# Rain_Collector_Inside_v2.net
KiCad netlist of a schematic drawn in EAGLE
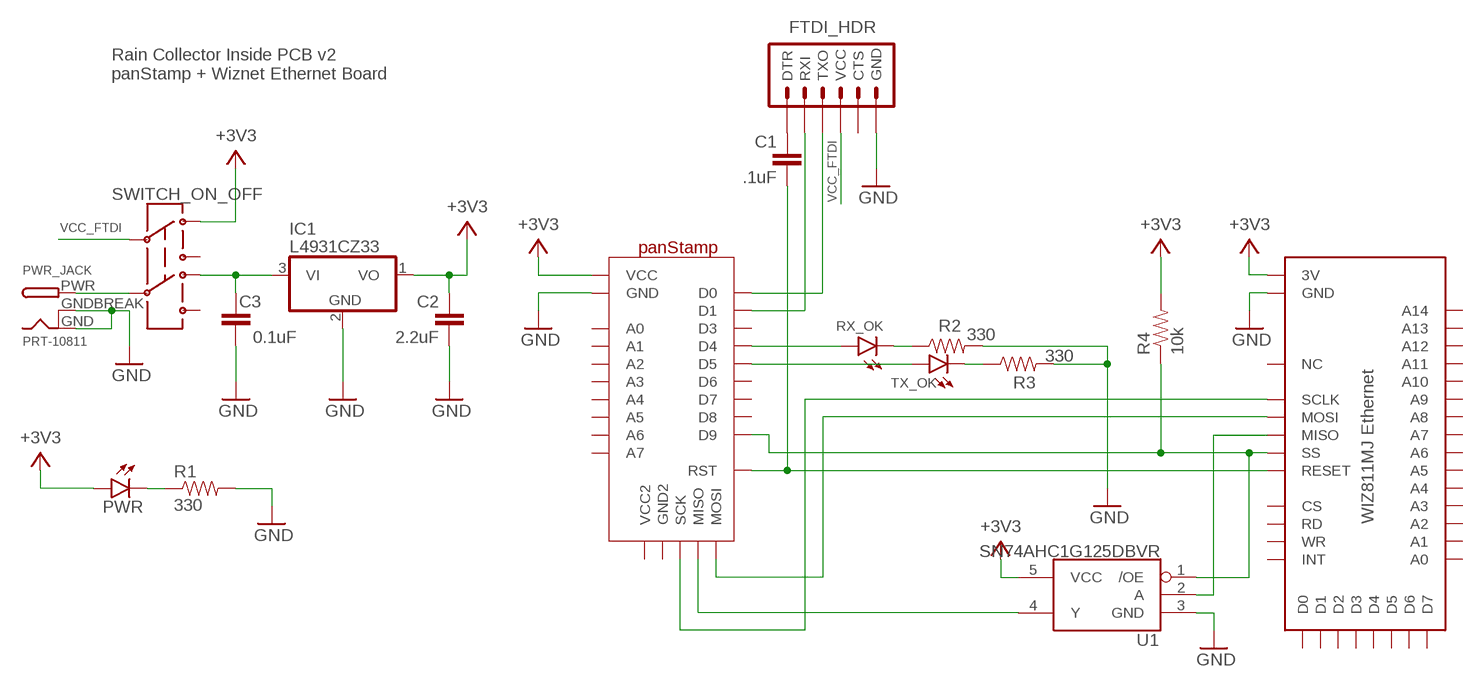
[diagram p0: schematic, sheet 1]

(export (version "E")
  (design (tool "Eeschema 10.0.6"))
  (components
    (comp (ref "C1")
      (value ".1uF")
      (footprint "eagle-import:CAP-PTH-5MM")
      (libsource (lib "eagle-import") (part "CAPPTH1"))
    )
    (comp (ref "C2")
      (value "2.2uF")
      (footprint "eagle-import:CAP-PTH-5MM")
      (libsource (lib "eagle-import") (part "CAPPTH1"))
    )
    (comp (ref "C3")
      (value "0.1uF")
      (footprint "eagle-import:CAP-PTH-5MM")
      (libsource (lib "eagle-import") (part "CAPPTH1"))
    )
    (comp (ref "FTDI_HDR")
      (value "ARDUINO_SERIAL_PROGRAMLONGPADS")
      (footprint "eagle-import:1X06_LONGPADS")
      (libsource (lib "eagle-import") (part "ARDUINO_SERIAL_PROGRAMLONGPADS"))
    )
    (comp (ref "IC1")
      (value "L4931CZ33")
      (footprint "eagle-import:TO92")
      (libsource (lib "eagle-import") (part "78ZL15"))
    )
    (comp (ref "PANSTAMP")
      (value "PANSTAMP_SPI")
      (footprint "eagle-import:PANSTAMP_SPI")
      (libsource (lib "eagle-import") (part "PANSTAMP_SPI"))
    )
    (comp (ref "PWR")
      (value "LED5MM")
      (footprint "eagle-import:LED5MM")
      (libsource (lib "eagle-import") (part "LED5MM"))
    )
    (comp (ref "PWR_JACK")
      (value "PRT-10811")
      (footprint "eagle-import:DCJACK_2MM_PTH")
      (libsource (lib "eagle-import") (part "DCBARRELPTH"))
    )
    (comp (ref "R1")
      (value "330")
      (footprint "eagle-import:AXIAL-0.4")
      (libsource (lib "eagle-import") (part "RESISTORPTH-1/4W"))
    )
    (comp (ref "R2")
      (value "330")
      (footprint "eagle-import:AXIAL-0.4")
      (libsource (lib "eagle-import") (part "RESISTORPTH-1/4W"))
    )
    (comp (ref "R3")
      (value "330")
      (footprint "eagle-import:AXIAL-0.4")
      (libsource (lib "eagle-import") (part "RESISTORPTH-1/4W"))
    )
    (comp (ref "R4")
      (value "10k")
      (footprint "eagle-import:AXIAL-0.4")
      (libsource (lib "eagle-import") (part "RESISTORPTH-1/4W"))
    )
    (comp (ref "RX_OK")
      (value "LED5MM")
      (footprint "eagle-import:LED5MM")
      (libsource (lib "eagle-import") (part "LED5MM"))
    )
    (comp (ref "SWITCH_ON_OFF")
      (value "401-2001-ND")
      (footprint "eagle-import:SWITCH_DPDT_PTH")
      (libsource (lib "eagle-import") (part "SWITCH_DPDTPTH"))
    )
    (comp (ref "TX_OK")
      (value "LED5MM")
      (footprint "eagle-import:LED5MM")
      (libsource (lib "eagle-import") (part "LED5MM"))
    )
    (comp (ref "U$2")
      (value "WIZ811MJ")
      (footprint "eagle-import:WIZ811MJ")
      (libsource (lib "eagle-import") (part "WIZ811MJ"))
    )
    (comp (ref "U1")
      (value "SN74AHC1G125DBVR")
      (footprint "eagle-import:SOT23-5")
      (libsource (lib "eagle-import") (part "74AHC1G125"))
    )
  )
  (nets
    (net (code "1") (name "+3V3") (class "Default")
      (node (ref "C2") (pin "1") (pinfunction "1_1") (pintype "passive"))
      (node (ref "IC1") (pin "1") (pinfunction "VO_1") (pintype "passive"))
      (node (ref "PANSTAMP") (pin "VCC") (pinfunction "VCC_VCC") (pintype "power_in"))
      (node (ref "PWR") (pin "A") (pinfunction "A_A") (pintype "passive"))
      (node (ref "R4") (pin "P$2") (pinfunction "2_P$2") (pintype "passive"))
      (node (ref "SWITCH_ON_OFF") (pin "1") (pinfunction "1_1") (pintype "bidirectional"))
      (node (ref "U$2") (pin "3V@1") (pinfunction "3V_3V@1") (pintype "power_in"))
      (node (ref "U$2") (pin "3V@2") (pinfunction "3V_3V@2") (pintype "power_in"))
      (node (ref "U1") (pin "5") (pinfunction "VCC_5") (pintype "bidirectional"))
    )
    (net (code "2") (name "/GND2") (class "Default")
      (node (ref "PANSTAMP") (pin "GND2") (pinfunction "GND2_GND2") (pintype "power_in"))
    )
    (net (code "3") (name "/VCC2") (class "Default")
      (node (ref "PANSTAMP") (pin "VCC2") (pinfunction "VCC2_VCC2") (pintype "power_in"))
    )
    (net (code "4") (name "/VCC_FTDI") (class "Default")
      (node (ref "FTDI_HDR") (pin "4") (pinfunction "VCC_4") (pintype "passive"))
      (node (ref "SWITCH_ON_OFF") (pin "2") (pinfunction "2_2") (pintype "bidirectional"))
    )
    (net (code "5") (name "GND") (class "Default")
      (node (ref "C2") (pin "2") (pinfunction "2_2") (pintype "passive"))
      (node (ref "C3") (pin "2") (pinfunction "2_2") (pintype "passive"))
      (node (ref "FTDI_HDR") (pin "6") (pinfunction "GND_6") (pintype "passive"))
      (node (ref "IC1") (pin "2") (pinfunction "GND_2") (pintype "passive"))
      (node (ref "PANSTAMP") (pin "GND$1") (pinfunction "GND_GND$1") (pintype "power_in"))
      (node (ref "PANSTAMP") (pin "GND$15") (pinfunction "GND_GND$15") (pintype "power_in"))
      (node (ref "PANSTAMP") (pin "GND$23") (pinfunction "GND_GND$23") (pintype "power_in"))
      (node (ref "PANSTAMP") (pin "GND$24") (pinfunction "GND_GND$24") (pintype "power_in"))
      (node (ref "PANSTAMP") (pin "GND$7") (pinfunction "GND_GND$7") (pintype "power_in"))
      (node (ref "PWR_JACK") (pin "GND") (pinfunction "GND_GND") (pintype "power_in"))
      (node (ref "PWR_JACK") (pin "GNDBREAK") (pinfunction "GNDBREAK_GNDBREAK") (pintype "power_in"))
      (node (ref "R1") (pin "P$2") (pinfunction "2_P$2") (pintype "passive"))
      (node (ref "R2") (pin "P$2") (pinfunction "2_P$2") (pintype "passive"))
      (node (ref "R3") (pin "P$2") (pinfunction "2_P$2") (pintype "passive"))
      (node (ref "U$2") (pin "GND@1") (pinfunction "GND_GND@1") (pintype "power_in"))
      (node (ref "U$2") (pin "GND@2") (pinfunction "GND_GND@2") (pintype "power_in"))
      (node (ref "U$2") (pin "GND@3") (pinfunction "GND_GND@3") (pintype "power_in"))
      (node (ref "U$2") (pin "GND@4") (pinfunction "GND_GND@4") (pintype "power_in"))
      (node (ref "U$2") (pin "GND@5") (pinfunction "GND_GND@5") (pintype "power_in"))
      (node (ref "U1") (pin "3") (pinfunction "GND_3") (pintype "bidirectional"))
    )
    (net (code "6") (name "Net-(FTDI_HDR-DTR)") (class "Default")
      (node (ref "C1") (pin "1") (pinfunction "1_1") (pintype "passive"))
      (node (ref "FTDI_HDR") (pin "1") (pinfunction "DTR_1") (pintype "passive"))
    )
    (net (code "7") (name "Net-(FTDI_HDR-RXI)") (class "Default")
      (node (ref "FTDI_HDR") (pin "2") (pinfunction "RXI_2") (pintype "passive"))
      (node (ref "PANSTAMP") (pin "D1") (pinfunction "D1_D1") (pintype "bidirectional"))
    )
    (net (code "8") (name "Net-(FTDI_HDR-TXO)") (class "Default")
      (node (ref "FTDI_HDR") (pin "3") (pinfunction "TXO_3") (pintype "passive"))
      (node (ref "PANSTAMP") (pin "D0") (pinfunction "D0_D0") (pintype "bidirectional"))
    )
    (net (code "9") (name "Net-(IC1-VI)") (class "Default")
      (node (ref "C3") (pin "1") (pinfunction "1_1") (pintype "passive"))
      (node (ref "IC1") (pin "3") (pinfunction "VI_3") (pintype "input"))
      (node (ref "SWITCH_ON_OFF") (pin "4") (pinfunction "4_4") (pintype "bidirectional"))
    )
    (net (code "10") (name "Net-(PANSTAMP-PadD4)") (class "Default")
      (node (ref "PANSTAMP") (pin "D4") (pinfunction "D4_D4") (pintype "bidirectional"))
      (node (ref "RX_OK") (pin "A") (pinfunction "A_A") (pintype "passive"))
    )
    (net (code "11") (name "Net-(PANSTAMP-PadD5)") (class "Default")
      (node (ref "PANSTAMP") (pin "D5") (pinfunction "D5_D5") (pintype "bidirectional"))
      (node (ref "TX_OK") (pin "A") (pinfunction "A_A") (pintype "passive"))
    )
    (net (code "12") (name "Net-(PANSTAMP-PadMOSI)") (class "Default")
      (node (ref "PANSTAMP") (pin "MOSI") (pinfunction "MOSI_MOSI") (pintype "bidirectional"))
      (node (ref "U$2") (pin "MOSI") (pinfunction "MOSI_MOSI") (pintype "bidirectional"))
    )
    (net (code "13") (name "Net-(PANSTAMP-PadSCK)") (class "Default")
      (node (ref "PANSTAMP") (pin "SCK") (pinfunction "SCK_SCK") (pintype "bidirectional"))
      (node (ref "U$2") (pin "SCLK") (pinfunction "SCLK_SCLK") (pintype "bidirectional"))
    )
    (net (code "14") (name "Net-(PANSTAMP-RST)") (class "Default")
      (node (ref "C1") (pin "2") (pinfunction "2_2") (pintype "passive"))
      (node (ref "PANSTAMP") (pin "RESET") (pinfunction "RST_RESET") (pintype "input"))
      (node (ref "U$2") (pin "RESET") (pinfunction "RESET_RESET") (pintype "input"))
    )
    (net (code "15") (name "Net-(PWR-C)") (class "Default")
      (node (ref "PWR") (pin "K") (pinfunction "C_K") (pintype "passive"))
      (node (ref "R1") (pin "P$1") (pinfunction "1_P$1") (pintype "passive"))
    )
    (net (code "16") (name "Net-(PWR_JACK-PadPWR)") (class "Default")
      (node (ref "PWR_JACK") (pin "PWR") (pinfunction "PWR_PWR") (pintype "power_in"))
      (node (ref "SWITCH_ON_OFF") (pin "5") (pinfunction "5_5") (pintype "bidirectional"))
    )
    (net (code "17") (name "Net-(R2-1)") (class "Default")
      (node (ref "R2") (pin "P$1") (pinfunction "1_P$1") (pintype "passive"))
      (node (ref "RX_OK") (pin "K") (pinfunction "C_K") (pintype "passive"))
    )
    (net (code "18") (name "Net-(R3-1)") (class "Default")
      (node (ref "R3") (pin "P$1") (pinfunction "1_P$1") (pintype "passive"))
      (node (ref "TX_OK") (pin "K") (pinfunction "C_K") (pintype "passive"))
    )
    (net (code "19") (name "Net-(R4-1)") (class "Default")
      (node (ref "PANSTAMP") (pin "D9") (pinfunction "D9_D9") (pintype "bidirectional"))
      (node (ref "R4") (pin "P$1") (pinfunction "1_P$1") (pintype "passive"))
      (node (ref "U$2") (pin "SCS") (pinfunction "SS_SCS") (pintype "bidirectional"))
      (node (ref "U1") (pin "1") (pinfunction "/OE_1") (pintype "bidirectional"))
    )
    (net (code "20") (name "Net-(U1-A)") (class "Default")
      (node (ref "U$2") (pin "MISO") (pinfunction "MISO_MISO") (pintype "bidirectional"))
      (node (ref "U1") (pin "2") (pinfunction "A_2") (pintype "bidirectional"))
    )
    (net (code "21") (name "Net-(U1-Y)") (class "Default")
      (node (ref "PANSTAMP") (pin "MISO") (pinfunction "MISO_MISO") (pintype "bidirectional"))
      (node (ref "U1") (pin "4") (pinfunction "Y_4") (pintype "bidirectional"))
    )
    (net (code "22") (name "unconnected-(FTDI_HDR-CTS-Pad5)") (class "Default")
      (node (ref "FTDI_HDR") (pin "5") (pinfunction "CTS_5") (pintype "passive"))
    )
    (net (code "23") (name "unconnected-(PANSTAMP-PadA0)") (class "Default")
      (node (ref "PANSTAMP") (pin "A0") (pinfunction "A0_A0") (pintype "bidirectional"))
    )
    (net (code "24") (name "unconnected-(PANSTAMP-PadA1)") (class "Default")
      (node (ref "PANSTAMP") (pin "A1") (pinfunction "A1_A1") (pintype "bidirectional"))
    )
    (net (code "25") (name "unconnected-(PANSTAMP-PadA2)") (class "Default")
      (node (ref "PANSTAMP") (pin "A2") (pinfunction "A2_A2") (pintype "bidirectional"))
    )
    (net (code "26") (name "unconnected-(PANSTAMP-PadA3)") (class "Default")
      (node (ref "PANSTAMP") (pin "A3") (pinfunction "A3_A3") (pintype "bidirectional"))
    )
    (net (code "27") (name "unconnected-(PANSTAMP-PadA4)") (class "Default")
      (node (ref "PANSTAMP") (pin "A4") (pinfunction "A4_A4") (pintype "bidirectional"))
    )
    (net (code "28") (name "unconnected-(PANSTAMP-PadA5)") (class "Default")
      (node (ref "PANSTAMP") (pin "A5") (pinfunction "A5_A5") (pintype "bidirectional"))
    )
    (net (code "29") (name "unconnected-(PANSTAMP-PadA6)") (class "Default")
      (node (ref "PANSTAMP") (pin "A6") (pinfunction "A6_A6") (pintype "bidirectional"))
    )
    (net (code "30") (name "unconnected-(PANSTAMP-PadA7)") (class "Default")
      (node (ref "PANSTAMP") (pin "A7") (pinfunction "A7_A7") (pintype "bidirectional"))
    )
    (net (code "31") (name "unconnected-(PANSTAMP-PadD3)") (class "Default")
      (node (ref "PANSTAMP") (pin "D3") (pinfunction "D3_D3") (pintype "bidirectional"))
    )
    (net (code "32") (name "unconnected-(PANSTAMP-PadD6)") (class "Default")
      (node (ref "PANSTAMP") (pin "D6") (pinfunction "D6_D6") (pintype "bidirectional"))
    )
    (net (code "33") (name "unconnected-(PANSTAMP-PadD7)") (class "Default")
      (node (ref "PANSTAMP") (pin "D7") (pinfunction "D7_D7") (pintype "bidirectional"))
    )
    (net (code "34") (name "unconnected-(PANSTAMP-PadD8)") (class "Default")
      (node (ref "PANSTAMP") (pin "D8") (pinfunction "D8_D8") (pintype "bidirectional"))
    )
    (net (code "35") (name "unconnected-(SWITCH_ON_OFF-Pad3)") (class "Default")
      (node (ref "SWITCH_ON_OFF") (pin "3") (pinfunction "3_3") (pintype "bidirectional"))
    )
    (net (code "36") (name "unconnected-(SWITCH_ON_OFF-Pad6)") (class "Default")
      (node (ref "SWITCH_ON_OFF") (pin "6") (pinfunction "6_6") (pintype "bidirectional"))
    )
    (net (code "37") (name "unconnected-(U$2-PadA0)") (class "Default")
      (node (ref "U$2") (pin "A0") (pinfunction "A0_A0") (pintype "bidirectional"))
    )
    (net (code "38") (name "unconnected-(U$2-PadA1)") (class "Default")
      (node (ref "U$2") (pin "A1") (pinfunction "A1_A1") (pintype "bidirectional"))
    )
    (net (code "39") (name "unconnected-(U$2-PadA2)") (class "Default")
      (node (ref "U$2") (pin "A2") (pinfunction "A2_A2") (pintype "bidirectional"))
    )
    (net (code "40") (name "unconnected-(U$2-PadA3)") (class "Default")
      (node (ref "U$2") (pin "A3") (pinfunction "A3_A3") (pintype "bidirectional"))
    )
    (net (code "41") (name "unconnected-(U$2-PadA4)") (class "Default")
      (node (ref "U$2") (pin "A4") (pinfunction "A4_A4") (pintype "bidirectional"))
    )
    (net (code "42") (name "unconnected-(U$2-PadA5)") (class "Default")
      (node (ref "U$2") (pin "A5") (pinfunction "A5_A5") (pintype "bidirectional"))
    )
    (net (code "43") (name "unconnected-(U$2-PadA6)") (class "Default")
      (node (ref "U$2") (pin "A6") (pinfunction "A6_A6") (pintype "bidirectional"))
    )
    (net (code "44") (name "unconnected-(U$2-PadA7)") (class "Default")
      (node (ref "U$2") (pin "A7") (pinfunction "A7_A7") (pintype "bidirectional"))
    )
    (net (code "45") (name "unconnected-(U$2-PadA8)") (class "Default")
      (node (ref "U$2") (pin "A8") (pinfunction "A8_A8") (pintype "bidirectional"))
    )
    (net (code "46") (name "unconnected-(U$2-PadA9)") (class "Default")
      (node (ref "U$2") (pin "A9") (pinfunction "A9_A9") (pintype "bidirectional"))
    )
    (net (code "47") (name "unconnected-(U$2-PadA10)") (class "Default")
      (node (ref "U$2") (pin "A10") (pinfunction "A10_A10") (pintype "bidirectional"))
    )
    (net (code "48") (name "unconnected-(U$2-PadA11)") (class "Default")
      (node (ref "U$2") (pin "A11") (pinfunction "A11_A11") (pintype "bidirectional"))
    )
    (net (code "49") (name "unconnected-(U$2-PadA12)") (class "Default")
      (node (ref "U$2") (pin "A12") (pinfunction "A12_A12") (pintype "bidirectional"))
    )
    (net (code "50") (name "unconnected-(U$2-PadA13)") (class "Default")
      (node (ref "U$2") (pin "A13") (pinfunction "A13_A13") (pintype "bidirectional"))
    )
    (net (code "51") (name "unconnected-(U$2-PadA14)") (class "Default")
      (node (ref "U$2") (pin "A14") (pinfunction "A14_A14") (pintype "bidirectional"))
    )
    (net (code "52") (name "unconnected-(U$2-PadCS)") (class "Default")
      (node (ref "U$2") (pin "CS") (pinfunction "CS_CS") (pintype "bidirectional"))
    )
    (net (code "53") (name "unconnected-(U$2-PadD0)") (class "Default")
      (node (ref "U$2") (pin "D0") (pinfunction "D0_D0") (pintype "bidirectional"))
    )
    (net (code "54") (name "unconnected-(U$2-PadD1)") (class "Default")
      (node (ref "U$2") (pin "D1") (pinfunction "D1_D1") (pintype "bidirectional"))
    )
    (net (code "55") (name "unconnected-(U$2-PadD2)") (class "Default")
      (node (ref "U$2") (pin "D2") (pinfunction "D2_D2") (pintype "bidirectional"))
    )
    (net (code "56") (name "unconnected-(U$2-PadD3)") (class "Default")
      (node (ref "U$2") (pin "D3") (pinfunction "D3_D3") (pintype "bidirectional"))
    )
    (net (code "57") (name "unconnected-(U$2-PadD4)") (class "Default")
      (node (ref "U$2") (pin "D4") (pinfunction "D4_D4") (pintype "bidirectional"))
    )
    (net (code "58") (name "unconnected-(U$2-PadD5)") (class "Default")
      (node (ref "U$2") (pin "D5") (pinfunction "D5_D5") (pintype "bidirectional"))
    )
    (net (code "59") (name "unconnected-(U$2-PadD6)") (class "Default")
      (node (ref "U$2") (pin "D6") (pinfunction "D6_D6") (pintype "bidirectional"))
    )
    (net (code "60") (name "unconnected-(U$2-PadD7)") (class "Default")
      (node (ref "U$2") (pin "D7") (pinfunction "D7_D7") (pintype "bidirectional"))
    )
    (net (code "61") (name "unconnected-(U$2-PadINT)") (class "Default")
      (node (ref "U$2") (pin "INT") (pinfunction "INT_INT") (pintype "bidirectional"))
    )
    (net (code "62") (name "unconnected-(U$2-PadNC)") (class "Default")
      (node (ref "U$2") (pin "NC") (pinfunction "NC_NC") (pintype "no_connect"))
    )
    (net (code "63") (name "unconnected-(U$2-PadRD)") (class "Default")
      (node (ref "U$2") (pin "RD") (pinfunction "RD_RD") (pintype "bidirectional"))
    )
    (net (code "64") (name "unconnected-(U$2-PadWR)") (class "Default")
      (node (ref "U$2") (pin "WR") (pinfunction "WR_WR") (pintype "bidirectional"))
    )
  )
)
